# WeMos_D1_mini.net
KiCad netlist of a schematic drawn in EAGLE
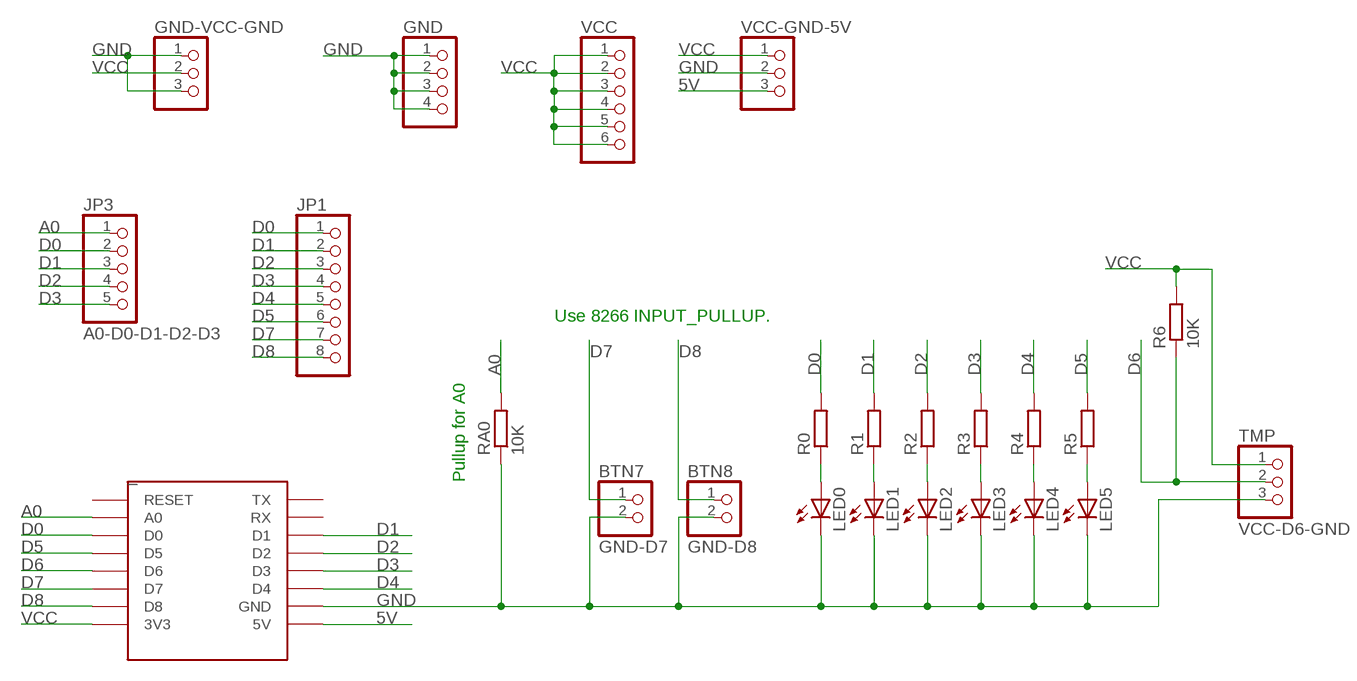
[diagram p0: schematic, sheet 1]

(export (version "E")
  (design (tool "Eeschema 10.0.6"))
  (components
    (comp (ref "BTN7")
      (value "GND-D7")
      (footprint "eagle-import:1X02_OCT")
      (libsource (lib "eagle-import") (part "PINHD-1X2/OCT"))
    )
    (comp (ref "BTN8")
      (value "GND-D8")
      (footprint "eagle-import:1X02_OCT")
      (libsource (lib "eagle-import") (part "PINHD-1X2/OCT"))
    )
    (comp (ref "GND")
      (value "PINHD-1X4/OCT")
      (footprint "eagle-import:1X04_OCT")
      (libsource (lib "eagle-import") (part "PINHD-1X4/OCT"))
    )
    (comp (ref "GND-VCC-GND")
      (value "PINHD-1X3/OCT")
      (footprint "eagle-import:1X03_OCT")
      (libsource (lib "eagle-import") (part "PINHD-1X3/OCT"))
    )
    (comp (ref "JP1")
      (value "PINHD-1X8/OCT")
      (footprint "eagle-import:1X08_OCT")
      (libsource (lib "eagle-import") (part "PINHD-1X8/OCT"))
    )
    (comp (ref "JP3")
      (value "A0-D0-D1-D2-D3")
      (footprint "eagle-import:1X05_OCT")
      (libsource (lib "eagle-import") (part "PINHD-1X5/OCT"))
    )
    (comp (ref "LED0")
      (value "LED3MM")
      (footprint "eagle-import:LED3MM")
      (libsource (lib "eagle-import") (part "LED3MM"))
    )
    (comp (ref "LED1")
      (value "LED3MM")
      (footprint "eagle-import:LED3MM")
      (libsource (lib "eagle-import") (part "LED3MM"))
    )
    (comp (ref "LED2")
      (value "LED3MM")
      (footprint "eagle-import:LED3MM")
      (libsource (lib "eagle-import") (part "LED3MM"))
    )
    (comp (ref "LED3")
      (value "LED3MM")
      (footprint "eagle-import:LED3MM")
      (libsource (lib "eagle-import") (part "LED3MM"))
    )
    (comp (ref "LED4")
      (value "LED3MM")
      (footprint "eagle-import:LED3MM")
      (libsource (lib "eagle-import") (part "LED3MM"))
    )
    (comp (ref "LED5")
      (value "LED3MM")
      (footprint "eagle-import:LED3MM")
      (libsource (lib "eagle-import") (part "LED3MM"))
    )
    (comp (ref "R0")
      (value "R-EU_0204/5")
      (footprint "eagle-import:0204_5")
      (libsource (lib "eagle-import") (part "R-EU_0204/5"))
    )
    (comp (ref "R1")
      (value "R-EU_0204/5")
      (footprint "eagle-import:0204_5")
      (libsource (lib "eagle-import") (part "R-EU_0204/5"))
    )
    (comp (ref "R2")
      (value "R-EU_0204/5")
      (footprint "eagle-import:0204_5")
      (libsource (lib "eagle-import") (part "R-EU_0204/5"))
    )
    (comp (ref "R3")
      (value "R-EU_0204/5")
      (footprint "eagle-import:0204_5")
      (libsource (lib "eagle-import") (part "R-EU_0204/5"))
    )
    (comp (ref "R4")
      (value "R-EU_0204/5")
      (footprint "eagle-import:0204_5")
      (libsource (lib "eagle-import") (part "R-EU_0204/5"))
    )
    (comp (ref "R5")
      (value "R-EU_0204/5")
      (footprint "eagle-import:0204_5")
      (libsource (lib "eagle-import") (part "R-EU_0204/5"))
    )
    (comp (ref "R6")
      (value "10K")
      (footprint "eagle-import:0204_5")
      (libsource (lib "eagle-import") (part "R-EU_0204/5"))
    )
    (comp (ref "RA0")
      (value "10K")
      (footprint "eagle-import:0204_5")
      (libsource (lib "eagle-import") (part "R-EU_0204/5"))
    )
    (comp (ref "TMP")
      (value "VCC-D6-GND")
      (footprint "eagle-import:1X03_OCT")
      (libsource (lib "eagle-import") (part "PINHD-1X3/OCT"))
    )
    (comp (ref "VCC")
      (value "PINHD-1X6/OCT")
      (footprint "eagle-import:1X06_OCT")
      (libsource (lib "eagle-import") (part "PINHD-1X6/OCT"))
    )
    (comp (ref "VCC-GND-5V")
      (value "PINHD-1X3/OCT")
      (footprint "eagle-import:1X03_OCT")
      (libsource (lib "eagle-import") (part "PINHD-1X3/OCT"))
    )
    (comp (ref "_")
      (value "WEMOS-D1-MINI")
      (footprint "eagle-import:WEMOS-D1-MINI")
      (libsource (lib "eagle-import") (part "WEMOS-D1-MINI"))
    )
  )
  (nets
    (net (code "1") (name "/5V") (class "Default")
      (node (ref "VCC-GND-5V") (pin "3") (pinfunction "3_3") (pintype "passive"))
      (node (ref "_") (pin "5V") (pinfunction "5V_5V") (pintype "bidirectional"))
    )
    (net (code "2") (name "/A0") (class "Default")
      (node (ref "JP3") (pin "1") (pinfunction "1_1") (pintype "passive"))
      (node (ref "RA0") (pin "2") (pinfunction "2_2") (pintype "passive"))
      (node (ref "_") (pin "A0") (pinfunction "A0_A0") (pintype "bidirectional"))
    )
    (net (code "3") (name "/D0") (class "Default")
      (node (ref "JP1") (pin "1") (pinfunction "1_1") (pintype "passive"))
      (node (ref "JP3") (pin "2") (pinfunction "2_2") (pintype "passive"))
      (node (ref "R0") (pin "2") (pinfunction "2_2") (pintype "passive"))
      (node (ref "_") (pin "D0") (pinfunction "D0_D0") (pintype "bidirectional"))
    )
    (net (code "4") (name "/D1") (class "Default")
      (node (ref "JP1") (pin "2") (pinfunction "2_2") (pintype "passive"))
      (node (ref "JP3") (pin "3") (pinfunction "3_3") (pintype "passive"))
      (node (ref "R1") (pin "2") (pinfunction "2_2") (pintype "passive"))
      (node (ref "_") (pin "D1") (pinfunction "D1_D1") (pintype "bidirectional"))
    )
    (net (code "5") (name "/D2") (class "Default")
      (node (ref "JP1") (pin "3") (pinfunction "3_3") (pintype "passive"))
      (node (ref "JP3") (pin "4") (pinfunction "4_4") (pintype "passive"))
      (node (ref "R2") (pin "2") (pinfunction "2_2") (pintype "passive"))
      (node (ref "_") (pin "D2") (pinfunction "D2_D2") (pintype "bidirectional"))
    )
    (net (code "6") (name "/D3") (class "Default")
      (node (ref "JP1") (pin "4") (pinfunction "4_4") (pintype "passive"))
      (node (ref "JP3") (pin "5") (pinfunction "5_5") (pintype "passive"))
      (node (ref "R3") (pin "2") (pinfunction "2_2") (pintype "passive"))
      (node (ref "_") (pin "D3") (pinfunction "D3_D3") (pintype "bidirectional"))
    )
    (net (code "7") (name "/D4") (class "Default")
      (node (ref "JP1") (pin "5") (pinfunction "5_5") (pintype "passive"))
      (node (ref "R4") (pin "2") (pinfunction "2_2") (pintype "passive"))
      (node (ref "_") (pin "D4") (pinfunction "D4_D4") (pintype "bidirectional"))
    )
    (net (code "8") (name "/D5") (class "Default")
      (node (ref "JP1") (pin "6") (pinfunction "6_6") (pintype "passive"))
      (node (ref "R5") (pin "2") (pinfunction "2_2") (pintype "passive"))
      (node (ref "_") (pin "D5") (pinfunction "D5_D5") (pintype "bidirectional"))
    )
    (net (code "9") (name "/D6") (class "Default")
      (node (ref "R6") (pin "1") (pinfunction "1_1") (pintype "passive"))
      (node (ref "TMP") (pin "2") (pinfunction "2_2") (pintype "passive"))
      (node (ref "_") (pin "D6") (pinfunction "D6_D6") (pintype "bidirectional"))
    )
    (net (code "10") (name "/D7") (class "Default")
      (node (ref "BTN7") (pin "1") (pinfunction "1_1") (pintype "passive"))
      (node (ref "JP1") (pin "7") (pinfunction "7_7") (pintype "passive"))
      (node (ref "_") (pin "D7") (pinfunction "D7_D7") (pintype "bidirectional"))
    )
    (net (code "11") (name "/D8") (class "Default")
      (node (ref "BTN8") (pin "1") (pinfunction "1_1") (pintype "passive"))
      (node (ref "JP1") (pin "8") (pinfunction "8_8") (pintype "passive"))
      (node (ref "_") (pin "D8") (pinfunction "D8_D8") (pintype "bidirectional"))
    )
    (net (code "12") (name "/GND") (class "Default")
      (node (ref "BTN7") (pin "2") (pinfunction "2_2") (pintype "passive"))
      (node (ref "BTN8") (pin "2") (pinfunction "2_2") (pintype "passive"))
      (node (ref "GND") (pin "1") (pinfunction "1_1") (pintype "passive"))
      (node (ref "GND") (pin "2") (pinfunction "2_2") (pintype "passive"))
      (node (ref "GND") (pin "3") (pinfunction "3_3") (pintype "passive"))
      (node (ref "GND") (pin "4") (pinfunction "4_4") (pintype "passive"))
      (node (ref "GND-VCC-GND") (pin "1") (pinfunction "1_1") (pintype "passive"))
      (node (ref "GND-VCC-GND") (pin "3") (pinfunction "3_3") (pintype "passive"))
      (node (ref "LED0") (pin "K") (pinfunction "C_K") (pintype "passive"))
      (node (ref "LED1") (pin "K") (pinfunction "C_K") (pintype "passive"))
      (node (ref "LED2") (pin "K") (pinfunction "C_K") (pintype "passive"))
      (node (ref "LED3") (pin "K") (pinfunction "C_K") (pintype "passive"))
      (node (ref "LED4") (pin "K") (pinfunction "C_K") (pintype "passive"))
      (node (ref "LED5") (pin "K") (pinfunction "C_K") (pintype "passive"))
      (node (ref "RA0") (pin "1") (pinfunction "1_1") (pintype "passive"))
      (node (ref "TMP") (pin "3") (pinfunction "3_3") (pintype "passive"))
      (node (ref "VCC-GND-5V") (pin "2") (pinfunction "2_2") (pintype "passive"))
      (node (ref "_") (pin "GND") (pinfunction "GND_GND") (pintype "bidirectional"))
    )
    (net (code "13") (name "/VCC") (class "Default")
      (node (ref "GND-VCC-GND") (pin "2") (pinfunction "2_2") (pintype "passive"))
      (node (ref "R6") (pin "2") (pinfunction "2_2") (pintype "passive"))
      (node (ref "TMP") (pin "1") (pinfunction "1_1") (pintype "passive"))
      (node (ref "VCC") (pin "1") (pinfunction "1_1") (pintype "passive"))
      (node (ref "VCC") (pin "2") (pinfunction "2_2") (pintype "passive"))
      (node (ref "VCC") (pin "3") (pinfunction "3_3") (pintype "passive"))
      (node (ref "VCC") (pin "4") (pinfunction "4_4") (pintype "passive"))
      (node (ref "VCC") (pin "5") (pinfunction "5_5") (pintype "passive"))
      (node (ref "VCC") (pin "6") (pinfunction "6_6") (pintype "passive"))
      (node (ref "VCC-GND-5V") (pin "1") (pinfunction "1_1") (pintype "passive"))
      (node (ref "_") (pin "3V3") (pinfunction "3V3_3V3") (pintype "bidirectional"))
    )
    (net (code "14") (name "Net-(LED0-PadA)") (class "Default")
      (node (ref "LED0") (pin "A") (pinfunction "A_A") (pintype "passive"))
      (node (ref "R0") (pin "1") (pinfunction "1_1") (pintype "passive"))
    )
    (net (code "15") (name "Net-(LED1-PadA)") (class "Default")
      (node (ref "LED1") (pin "A") (pinfunction "A_A") (pintype "passive"))
      (node (ref "R1") (pin "1") (pinfunction "1_1") (pintype "passive"))
    )
    (net (code "16") (name "Net-(LED2-PadA)") (class "Default")
      (node (ref "LED2") (pin "A") (pinfunction "A_A") (pintype "passive"))
      (node (ref "R2") (pin "1") (pinfunction "1_1") (pintype "passive"))
    )
    (net (code "17") (name "Net-(LED3-PadA)") (class "Default")
      (node (ref "LED3") (pin "A") (pinfunction "A_A") (pintype "passive"))
      (node (ref "R3") (pin "1") (pinfunction "1_1") (pintype "passive"))
    )
    (net (code "18") (name "Net-(LED4-PadA)") (class "Default")
      (node (ref "LED4") (pin "A") (pinfunction "A_A") (pintype "passive"))
      (node (ref "R4") (pin "1") (pinfunction "1_1") (pintype "passive"))
    )
    (net (code "19") (name "Net-(LED5-PadA)") (class "Default")
      (node (ref "LED5") (pin "A") (pinfunction "A_A") (pintype "passive"))
      (node (ref "R5") (pin "1") (pinfunction "1_1") (pintype "passive"))
    )
    (net (code "20") (name "unconnected-(_-PadRESET)") (class "Default")
      (node (ref "_") (pin "RESET") (pinfunction "RESET_RESET") (pintype "bidirectional"))
    )
    (net (code "21") (name "unconnected-(_-PadRX)") (class "Default")
      (node (ref "_") (pin "RX") (pinfunction "RX_RX") (pintype "bidirectional"))
    )
    (net (code "22") (name "unconnected-(_-PadTX)") (class "Default")
      (node (ref "_") (pin "TX") (pinfunction "TX_TX") (pintype "bidirectional"))
    )
  )
)
